# MCU.net
KiCad netlist of a schematic drawn in Altium Designer
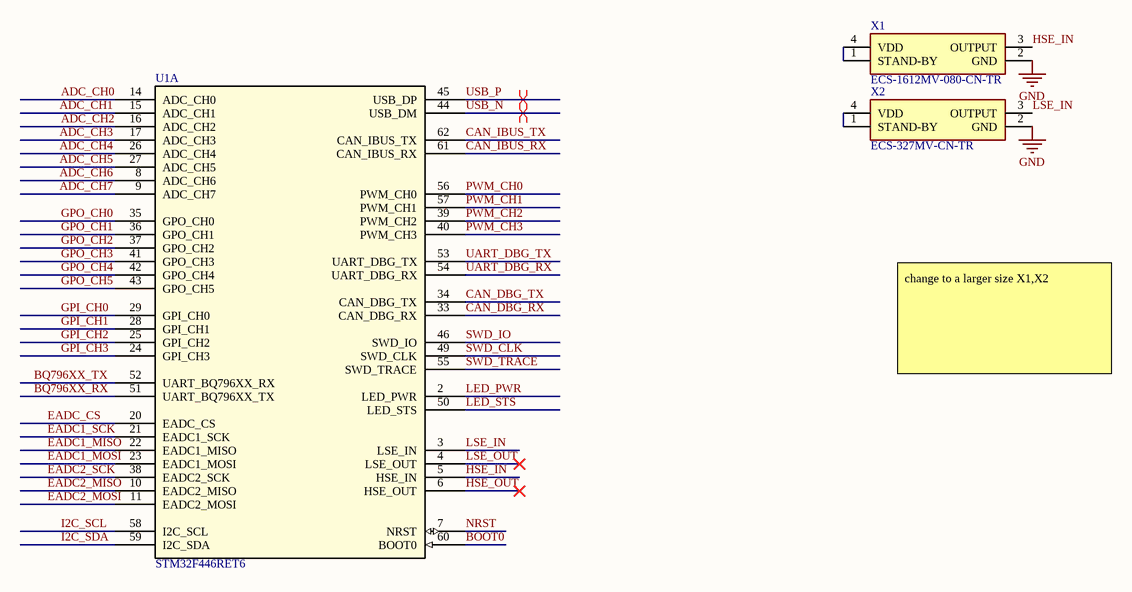
[diagram p0: MCU.SchDoc]

(export (version "E")
  (design (tool "Eeschema 10.0.6"))
  (components
    (comp (ref "U1")
      (value "STM32F446RET6")
      (footprint "LQFP64-STM32F446")
      (description "No Description Available")
      (fields (field (name "COPYRIGHT") "Copyright (C) 2023 Ultra Librarian. All rights reserved."))
      (libsource (lib "BMS_ShareComponentLibrary") (part "STM32F446RET6"))
    )
    (comp (ref "X1")
      (value "ECS-1612MV-080-CN-TR")
      (footprint "1612_OSXO_80")
      (description "Standard Clock Oscillators 8MHz CMOS 1.6-3.6V")
      (fields (field (name "MOUSER PART NUMBER") "520-1612MV-080-CNT"))
      (libsource (lib "BMS_ShareComponentLibrary") (part "8M OSXO ECS"))
    )
    (comp (ref "X2")
      (value "ECS-327MV-CN-TR")
      (footprint "1612_OSXO_32.768")
      (description "Standard Clock Oscillators 32.768kHz LVCMOS 1.6-3.6V")
      (fields (field (name "MOUSER PART NUMBER") "520-327MV-CNT"))
      (libsource (lib "BMS_ShareComponentLibrary") (part "32.768k OSXO ECS"))
    )
  )
  (nets
    (net (code "1") (name "/ADC_CH0") (class "Default")
      (node (ref "U1") (pin "14") (pinfunction "ADC_CH0_14") (pintype "passive"))
    )
    (net (code "2") (name "/ADC_CH1") (class "Default")
      (node (ref "U1") (pin "15") (pinfunction "ADC_CH1_15") (pintype "passive"))
    )
    (net (code "3") (name "/ADC_CH2") (class "Default")
      (node (ref "U1") (pin "16") (pinfunction "ADC_CH2_16") (pintype "passive"))
    )
    (net (code "4") (name "/ADC_CH3") (class "Default")
      (node (ref "U1") (pin "17") (pinfunction "ADC_CH3_17") (pintype "passive"))
    )
    (net (code "5") (name "/ADC_CH4") (class "Default")
      (node (ref "U1") (pin "26") (pinfunction "ADC_CH4_26") (pintype "passive"))
    )
    (net (code "6") (name "/ADC_CH5") (class "Default")
      (node (ref "U1") (pin "27") (pinfunction "ADC_CH5_27") (pintype "passive"))
    )
    (net (code "7") (name "/ADC_CH6") (class "Default")
      (node (ref "U1") (pin "8") (pinfunction "ADC_CH6_8") (pintype "passive"))
    )
    (net (code "8") (name "/ADC_CH7") (class "Default")
      (node (ref "U1") (pin "9") (pinfunction "ADC_CH7_9") (pintype "passive"))
    )
    (net (code "9") (name "/BOOT0") (class "Default")
      (node (ref "U1") (pin "60") (pinfunction "BOOT0_60") (pintype "input"))
    )
    (net (code "10") (name "/BQ796XX_RX") (class "Default")
      (node (ref "U1") (pin "51") (pinfunction "UART_BQ796XX_TX_51") (pintype "passive"))
    )
    (net (code "11") (name "/BQ796XX_TX") (class "Default")
      (node (ref "U1") (pin "52") (pinfunction "UART_BQ796XX_RX_52") (pintype "passive"))
    )
    (net (code "12") (name "/CAN_DBG_RX") (class "Default")
      (node (ref "U1") (pin "33") (pinfunction "CAN_DBG_RX_33") (pintype "passive"))
    )
    (net (code "13") (name "/CAN_DBG_TX") (class "Default")
      (node (ref "U1") (pin "34") (pinfunction "CAN_DBG_TX_34") (pintype "passive"))
    )
    (net (code "14") (name "/CAN_IBUS_RX") (class "Default")
      (node (ref "U1") (pin "61") (pinfunction "CAN_IBUS_RX_61") (pintype "passive"))
    )
    (net (code "15") (name "/CAN_IBUS_TX") (class "Default")
      (node (ref "U1") (pin "62") (pinfunction "CAN_IBUS_TX_62") (pintype "passive"))
    )
    (net (code "16") (name "/EADC1_MISO") (class "Default")
      (node (ref "U1") (pin "22") (pinfunction "EADC1_MISO_22") (pintype "passive"))
    )
    (net (code "17") (name "/EADC1_MOSI") (class "Default")
      (node (ref "U1") (pin "23") (pinfunction "EADC1_MOSI_23") (pintype "passive"))
    )
    (net (code "18") (name "/EADC1_SCK") (class "Default")
      (node (ref "U1") (pin "21") (pinfunction "EADC1_SCK_21") (pintype "passive"))
    )
    (net (code "19") (name "/EADC2_MISO") (class "Default")
      (node (ref "U1") (pin "10") (pinfunction "EADC2_MISO_10") (pintype "passive"))
    )
    (net (code "20") (name "/EADC2_MOSI") (class "Default")
      (node (ref "U1") (pin "11") (pinfunction "EADC2_MOSI_11") (pintype "passive"))
    )
    (net (code "21") (name "/EADC2_SCK") (class "Default")
      (node (ref "U1") (pin "38") (pinfunction "EADC2_SCK_38") (pintype "passive"))
    )
    (net (code "22") (name "/EADC_CS") (class "Default")
      (node (ref "U1") (pin "20") (pinfunction "EADC_CS_20") (pintype "passive"))
    )
    (net (code "23") (name "/GPI_CH0") (class "Default")
      (node (ref "U1") (pin "29") (pinfunction "GPI_CH0_29") (pintype "passive"))
    )
    (net (code "24") (name "/GPI_CH1") (class "Default")
      (node (ref "U1") (pin "28") (pinfunction "GPI_CH1_28") (pintype "passive"))
    )
    (net (code "25") (name "/GPI_CH2") (class "Default")
      (node (ref "U1") (pin "25") (pinfunction "GPI_CH2_25") (pintype "passive"))
    )
    (net (code "26") (name "/GPI_CH3") (class "Default")
      (node (ref "U1") (pin "24") (pinfunction "GPI_CH3_24") (pintype "passive"))
    )
    (net (code "27") (name "/GPO_CH0") (class "Default")
      (node (ref "U1") (pin "35") (pinfunction "GPO_CH0_35") (pintype "passive"))
    )
    (net (code "28") (name "/GPO_CH1") (class "Default")
      (node (ref "U1") (pin "36") (pinfunction "GPO_CH1_36") (pintype "passive"))
    )
    (net (code "29") (name "/GPO_CH2") (class "Default")
      (node (ref "U1") (pin "37") (pinfunction "GPO_CH2_37") (pintype "passive"))
    )
    (net (code "30") (name "/GPO_CH3") (class "Default")
      (node (ref "U1") (pin "41") (pinfunction "GPO_CH3_41") (pintype "passive"))
    )
    (net (code "31") (name "/GPO_CH4") (class "Default")
      (node (ref "U1") (pin "42") (pinfunction "GPO_CH4_42") (pintype "passive"))
    )
    (net (code "32") (name "/GPO_CH5") (class "Default")
      (node (ref "U1") (pin "43") (pinfunction "GPO_CH5_43") (pintype "passive"))
    )
    (net (code "33") (name "/HSE_IN") (class "Default")
      (node (ref "U1") (pin "5") (pinfunction "HSE_IN_5") (pintype "passive"))
      (node (ref "X1") (pin "3") (pinfunction "OUTPUT_3") (pintype "passive"))
    )
    (net (code "34") (name "/HSE_OUT") (class "Default")
      (node (ref "U1") (pin "6") (pinfunction "HSE_OUT_6") (pintype "passive+no_connect"))
    )
    (net (code "35") (name "/I2C_SCL") (class "Default")
      (node (ref "U1") (pin "58") (pinfunction "I2C_SCL_58") (pintype "passive"))
    )
    (net (code "36") (name "/I2C_SDA") (class "Default")
      (node (ref "U1") (pin "59") (pinfunction "I2C_SDA_59") (pintype "passive"))
    )
    (net (code "37") (name "/LED_PWR") (class "Default")
      (node (ref "U1") (pin "2") (pinfunction "LED_PWR_2") (pintype "passive"))
    )
    (net (code "38") (name "/LED_STS") (class "Default")
      (node (ref "U1") (pin "50") (pinfunction "LED_STS_50") (pintype "passive"))
    )
    (net (code "39") (name "/LSE_IN") (class "Default")
      (node (ref "U1") (pin "3") (pinfunction "LSE_IN_3") (pintype "passive"))
      (node (ref "X2") (pin "3") (pinfunction "OUTPUT_3") (pintype "passive"))
    )
    (net (code "40") (name "/LSE_OUT") (class "Default")
      (node (ref "U1") (pin "4") (pinfunction "LSE_OUT_4") (pintype "passive+no_connect"))
    )
    (net (code "41") (name "/NRST") (class "Default")
      (node (ref "U1") (pin "7") (pinfunction "NRST_7") (pintype "bidirectional"))
    )
    (net (code "42") (name "/PWM_CH0") (class "Default")
      (node (ref "U1") (pin "56") (pinfunction "PWM_CH0_56") (pintype "passive"))
    )
    (net (code "43") (name "/PWM_CH1") (class "Default")
      (node (ref "U1") (pin "57") (pinfunction "PWM_CH1_57") (pintype "passive"))
    )
    (net (code "44") (name "/PWM_CH2") (class "Default")
      (node (ref "U1") (pin "39") (pinfunction "PWM_CH2_39") (pintype "passive"))
    )
    (net (code "45") (name "/PWM_CH3") (class "Default")
      (node (ref "U1") (pin "40") (pinfunction "PWM_CH3_40") (pintype "passive"))
    )
    (net (code "46") (name "/SWD_CLK") (class "Default")
      (node (ref "U1") (pin "49") (pinfunction "SWD_CLK_49") (pintype "passive"))
    )
    (net (code "47") (name "/SWD_IO") (class "Default")
      (node (ref "U1") (pin "46") (pinfunction "SWD_IO_46") (pintype "passive"))
    )
    (net (code "48") (name "/SWD_TRACE") (class "Default")
      (node (ref "U1") (pin "55") (pinfunction "SWD_TRACE_55") (pintype "passive"))
    )
    (net (code "49") (name "/UART_DBG_RX") (class "Default")
      (node (ref "U1") (pin "54") (pinfunction "UART_DBG_RX_54") (pintype "passive"))
    )
    (net (code "50") (name "/UART_DBG_TX") (class "Default")
      (node (ref "U1") (pin "53") (pinfunction "UART_DBG_TX_53") (pintype "passive"))
    )
    (net (code "51") (name "/USB_N") (class "Default")
      (node (ref "U1") (pin "44") (pinfunction "USB_DM_44") (pintype "passive"))
    )
    (net (code "52") (name "/USB_P") (class "Default")
      (node (ref "U1") (pin "45") (pinfunction "USB_DP_45") (pintype "passive"))
    )
    (net (code "53") (name "GND") (class "Default")
      (node (ref "X1") (pin "2") (pinfunction "GND_2") (pintype "passive"))
      (node (ref "X2") (pin "2") (pinfunction "GND_2") (pintype "passive"))
    )
    (net (code "54") (name "Net-(X1-STAND-BY)") (class "Default")
      (node (ref "X1") (pin "1") (pinfunction "STAND-BY_1") (pintype "passive"))
      (node (ref "X1") (pin "4") (pinfunction "VDD_4") (pintype "passive"))
    )
    (net (code "55") (name "Net-(X2-STAND-BY)") (class "Default")
      (node (ref "X2") (pin "1") (pinfunction "STAND-BY_1") (pintype "passive"))
      (node (ref "X2") (pin "4") (pinfunction "VDD_4") (pintype "passive"))
    )
  )
)
